# SchemaA.net
KiCad netlist of a schematic drawn in Altium Designer
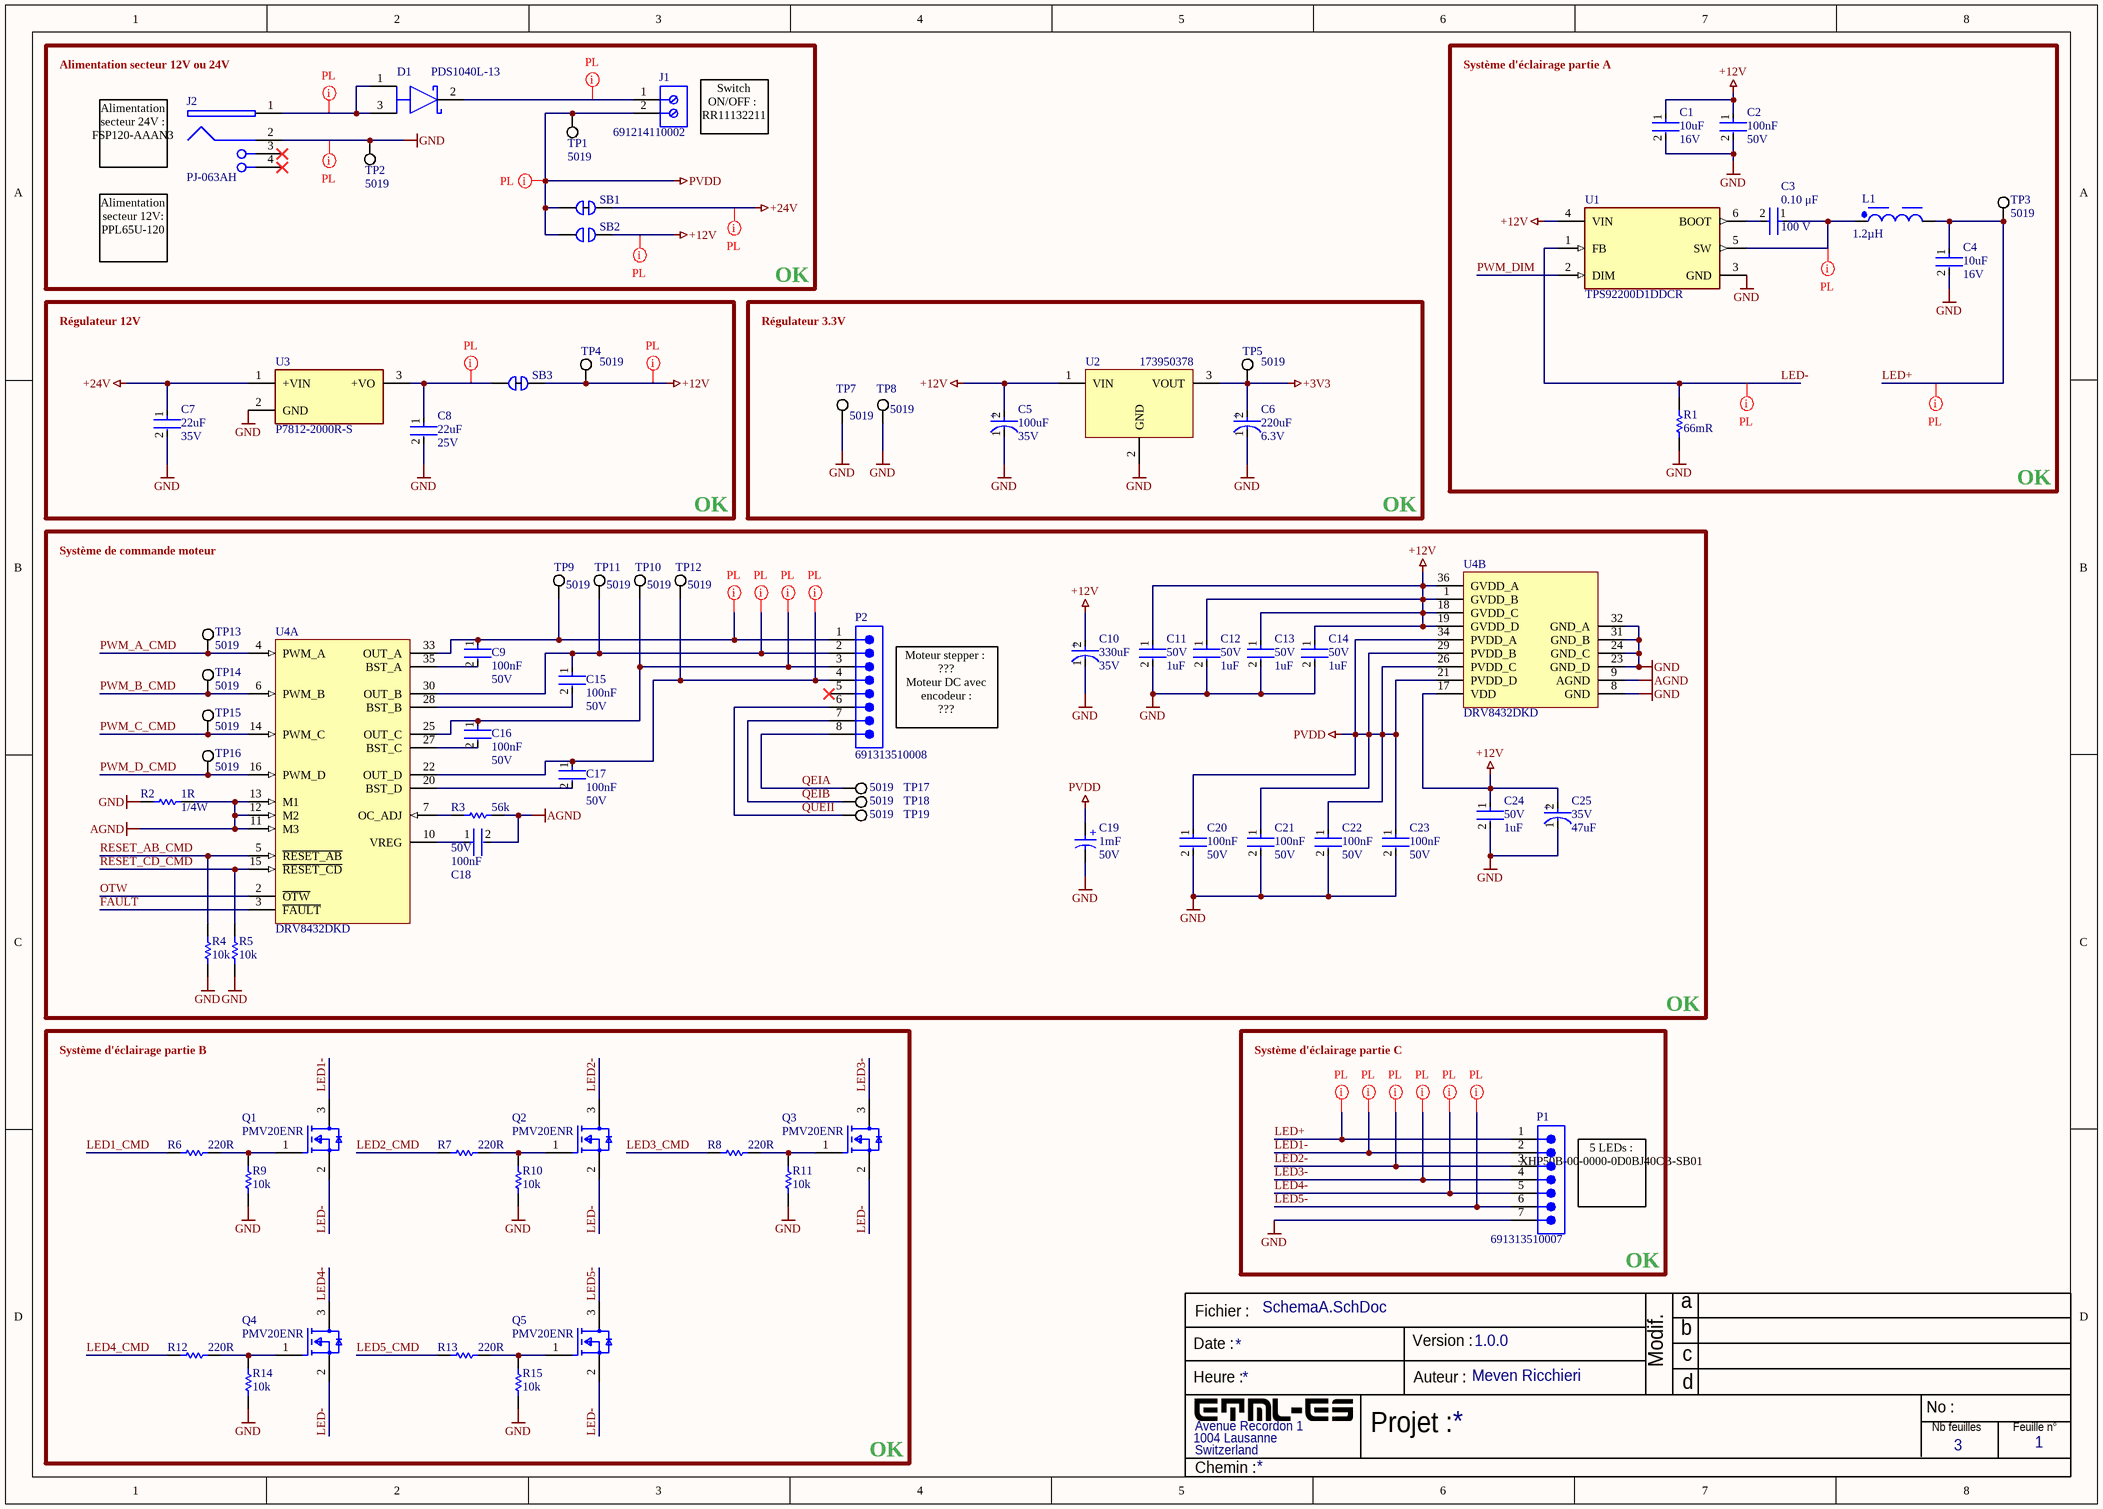
[diagram p0: SchemaA.SchDoc]

(export (version "E")
  (design (tool "Eeschema 10.0.6"))
  (components
    (comp (ref "C1")
      (value "CL21A106KOQNNNE")
      (footprint "FP-CL21-IPC_B")
      (description "CL21 Series 0805 10uF 16V ±10% Tolerance X5R Multilayer Ceramic Chip Capacitor")
      (fields
        (field (name "VOLTAGE") "16V")
        (field (name "CAPACITANCE") "10uF")
        (field (name "VOLTAGE RATING") "16V")
        (field (name "TOLERANCE") "10%")
      )
      (libsource (lib "Altium Content Vault") (part "b4654b650e69147ec39a6b967a45e02"))
    )
    (comp (ref "C2")
      (value "CL21B104KBCNNNC")
      (footprint "FP-CL21-IPC_C")
      (description "CL21 Series 0805 100nF 50V ±10% Tolerance X7R Multilayer Ceramic Chip Capacitor")
      (fields
        (field (name "TOLERANCE") "10%")
        (field (name "CAPACITANCE") "100nF")
        (field (name "VOLTAGE RATING") "50V")
        (field (name "VOLTAGE") "50V")
      )
      (libsource (lib "Altium Content Vault") (part "b4654b650e69147ec39a6b967a45e02"))
    )
    (comp (ref "C3")
      (value "C0805C104K1RACAUTO")
      (footprint "FP-C0805C-DN-MFG")
      (description "CAP CER 0.1UF 100V X7R 0805")
      (fields
        (field (name "MANUFACTURER") "KEMET")
        (field (name "CAPACITANCE") "0.10 μF")
        (field (name "TOLERANCE") "0.1")
        (field (name "VOLTAGE RATING") "100 V")
      )
      (libsource (lib "Altium Content Vault") (part "b4654b650e69147ec39a6b967a45e02"))
    )
    (comp (ref "C4")
      (value "CL21A106KOQNNNE")
      (footprint "FP-CL21-IPC_B")
      (description "CL21 Series 0805 10uF 16V ±10% Tolerance X5R Multilayer Ceramic Chip Capacitor")
      (fields
        (field (name "VOLTAGE") "16V")
        (field (name "CAPACITANCE") "10uF")
        (field (name "VOLTAGE RATING") "16V")
        (field (name "TOLERANCE") "10%")
      )
      (libsource (lib "Altium Content Vault") (part "b4654b650e69147ec39a6b967a45e02"))
    )
    (comp (ref "C5")
      (value "EEE-1VA101XP")
      (footprint "FP-SD8-MFG")
      (description "CAP ALUM 100UF 20% 35V SMD")
      (fields
        (field (name "CAPACITANCE") "100uF")
        (field (name "TOLERANCE") "20%")
        (field (name "VOLTAGE") "35V")
      )
      (libsource (lib "Altium Content Vault") (part "a00bbbee19879c290e62620ae7e47b1"))
    )
    (comp (ref "C6")
      (value "EEE-FK0J221P")
      (footprint "FP-FKD-MFG")
      (description "CAP ALUM 220UF 20% 6.3V SMD")
      (fields
        (field (name "VOLTAGE RATING") "6.3V")
        (field (name "VOLTAGE") "6.3V")
        (field (name "CAPACITANCE") "220uF")
        (field (name "TOLERANCE") "20%")
      )
      (libsource (lib "Altium Content Vault") (part "a00bbbee19879c290e62620ae7e47b1"))
    )
    (comp (ref "C7")
      (value "GMK325BJ226MM-P")
      (footprint "FP-1210-L_3_2_0_3-W_2_5_0-MFG")
      (description "None")
      (fields
        (field (name "CAPACITANCE") "22uF")
        (field (name "VOLTAGE RATING") "35V")
        (field (name "TOLERANCE") "20%")
      )
      (libsource (lib "Altium Content Vault") (part "02cd4be3c70576c341d710602a673aa"))
    )
    (comp (ref "C8")
      (value "22uF")
      (footprint "FP-CL21-IPC_C")
      (description "CL21 Series 0805 22uF 25V ±20% Tolerance X5R Multilayer Ceramic Chip Capacitor")
      (fields (field (name "VOLTAGE") "25V") (field (name "Comment") "CL21A226MAYNNNE"))
      (libsource (lib "Altium Content Vault") (part "b4654b650e69147ec39a6b967a45e02"))
    )
    (comp (ref "C9")
      (value "CL21B104KBCNNNC")
      (footprint "FP-CL21-IPC_C")
      (description "CL21 Series 0805 100nF 50V ±10% Tolerance X7R Multilayer Ceramic Chip Capacitor")
      (fields
        (field (name "TOLERANCE") "10%")
        (field (name "CAPACITANCE") "100nF")
        (field (name "VOLTAGE RATING") "50V")
        (field (name "VOLTAGE") "50V")
      )
      (libsource (lib "Altium Content Vault") (part "b4654b650e69147ec39a6b967a45e02"))
    )
    (comp (ref "C10")
      (value "EEE-1VA331P")
      (footprint "FP-SG-MFG")
      (description "CAP ALUM 330UF 20% 35V SMD")
      (fields
        (field (name "VOLTAGE") "35V")
        (field (name "TOLERANCE") "20%")
        (field (name "CAPACITANCE") "330uF")
      )
      (libsource (lib "Altium Content Vault") (part "a00bbbee19879c290e62620ae7e47b1"))
    )
    (comp (ref "C11")
      (value "CL21B105KBFNNNG")
      (footprint "FP-CL21-IPC_C")
      (description "CL21 Series 0805 1uF 50V ±10% Tolerance X7R Multilayer Ceramic Chip Capacitor")
      (fields
        (field (name "CAPACITANCE") "1uF")
        (field (name "VOLTAGE") "50V")
        (field (name "TOLERANCE") "10%")
      )
      (libsource (lib "Altium Content Vault") (part "b4654b650e69147ec39a6b967a45e02"))
    )
    (comp (ref "C12")
      (value "CL21B105KBFNNNG")
      (footprint "FP-CL21-IPC_C")
      (description "CL21 Series 0805 1uF 50V ±10% Tolerance X7R Multilayer Ceramic Chip Capacitor")
      (fields
        (field (name "CAPACITANCE") "1uF")
        (field (name "VOLTAGE") "50V")
        (field (name "TOLERANCE") "10%")
      )
      (libsource (lib "Altium Content Vault") (part "b4654b650e69147ec39a6b967a45e02"))
    )
    (comp (ref "C13")
      (value "CL21B105KBFNNNG")
      (footprint "FP-CL21-IPC_C")
      (description "CL21 Series 0805 1uF 50V ±10% Tolerance X7R Multilayer Ceramic Chip Capacitor")
      (fields
        (field (name "CAPACITANCE") "1uF")
        (field (name "VOLTAGE") "50V")
        (field (name "TOLERANCE") "10%")
      )
      (libsource (lib "Altium Content Vault") (part "b4654b650e69147ec39a6b967a45e02"))
    )
    (comp (ref "C14")
      (value "CL21B105KBFNNNG")
      (footprint "FP-CL21-IPC_C")
      (description "CL21 Series 0805 1uF 50V ±10% Tolerance X7R Multilayer Ceramic Chip Capacitor")
      (fields
        (field (name "CAPACITANCE") "1uF")
        (field (name "VOLTAGE") "50V")
        (field (name "TOLERANCE") "10%")
      )
      (libsource (lib "Altium Content Vault") (part "b4654b650e69147ec39a6b967a45e02"))
    )
    (comp (ref "C15")
      (value "CL21B104KBCNNNC")
      (footprint "FP-CL21-IPC_C")
      (description "CL21 Series 0805 100nF 50V ±10% Tolerance X7R Multilayer Ceramic Chip Capacitor")
      (fields
        (field (name "TOLERANCE") "10%")
        (field (name "CAPACITANCE") "100nF")
        (field (name "VOLTAGE RATING") "50V")
        (field (name "VOLTAGE") "50V")
      )
      (libsource (lib "Altium Content Vault") (part "b4654b650e69147ec39a6b967a45e02"))
    )
    (comp (ref "C16")
      (value "CL21B104KBCNNNC")
      (footprint "FP-CL21-IPC_C")
      (description "CL21 Series 0805 100nF 50V ±10% Tolerance X7R Multilayer Ceramic Chip Capacitor")
      (fields
        (field (name "TOLERANCE") "10%")
        (field (name "CAPACITANCE") "100nF")
        (field (name "VOLTAGE RATING") "50V")
        (field (name "VOLTAGE") "50V")
      )
      (libsource (lib "Altium Content Vault") (part "b4654b650e69147ec39a6b967a45e02"))
    )
    (comp (ref "C17")
      (value "CL21B104KBCNNNC")
      (footprint "FP-CL21-IPC_C")
      (description "CL21 Series 0805 100nF 50V ±10% Tolerance X7R Multilayer Ceramic Chip Capacitor")
      (fields
        (field (name "TOLERANCE") "10%")
        (field (name "CAPACITANCE") "100nF")
        (field (name "VOLTAGE RATING") "50V")
        (field (name "VOLTAGE") "50V")
      )
      (libsource (lib "Altium Content Vault") (part "b4654b650e69147ec39a6b967a45e02"))
    )
    (comp (ref "C18")
      (value "CL21B104KBCNNNC")
      (footprint "FP-CL21-IPC_C")
      (description "CL21 Series 0805 100nF 50V ±10% Tolerance X7R Multilayer Ceramic Chip Capacitor")
      (fields
        (field (name "TOLERANCE") "10%")
        (field (name "CAPACITANCE") "100nF")
        (field (name "VOLTAGE RATING") "50V")
        (field (name "VOLTAGE") "50V")
      )
      (libsource (lib "Altium Content Vault") (part "b4654b650e69147ec39a6b967a45e02"))
    )
    (comp (ref "C19")
      (value "865080663020")
      (footprint "WCAP-ASLI_D16H17")
      (description "865080663020 WCAP-ASLI Aluminum Electrolytic Capacitors")
      (fields
        (field (name "CAPACITANCE") "1mF")
        (field (name "VOLTAGE RATING") "50V")
        (field (name "TOLERANCE") "20%")
      )
      (libsource (lib "Altium Content Vault") (part "Capacitor_Polarized"))
    )
    (comp (ref "C20")
      (value "CL21B104KBCNNNC")
      (footprint "FP-CL21-IPC_C")
      (description "CL21 Series 0805 100nF 50V ±10% Tolerance X7R Multilayer Ceramic Chip Capacitor")
      (fields
        (field (name "TOLERANCE") "10%")
        (field (name "CAPACITANCE") "100nF")
        (field (name "VOLTAGE RATING") "50V")
        (field (name "VOLTAGE") "50V")
      )
      (libsource (lib "Altium Content Vault") (part "b4654b650e69147ec39a6b967a45e02"))
    )
    (comp (ref "C21")
      (value "CL21B104KBCNNNC")
      (footprint "FP-CL21-IPC_C")
      (description "CL21 Series 0805 100nF 50V ±10% Tolerance X7R Multilayer Ceramic Chip Capacitor")
      (fields
        (field (name "TOLERANCE") "10%")
        (field (name "CAPACITANCE") "100nF")
        (field (name "VOLTAGE RATING") "50V")
        (field (name "VOLTAGE") "50V")
      )
      (libsource (lib "Altium Content Vault") (part "b4654b650e69147ec39a6b967a45e02"))
    )
    (comp (ref "C22")
      (value "CL21B104KBCNNNC")
      (footprint "FP-CL21-IPC_C")
      (description "CL21 Series 0805 100nF 50V ±10% Tolerance X7R Multilayer Ceramic Chip Capacitor")
      (fields
        (field (name "TOLERANCE") "10%")
        (field (name "CAPACITANCE") "100nF")
        (field (name "VOLTAGE RATING") "50V")
        (field (name "VOLTAGE") "50V")
      )
      (libsource (lib "Altium Content Vault") (part "b4654b650e69147ec39a6b967a45e02"))
    )
    (comp (ref "C23")
      (value "CL21B104KBCNNNC")
      (footprint "FP-CL21-IPC_C")
      (description "CL21 Series 0805 100nF 50V ±10% Tolerance X7R Multilayer Ceramic Chip Capacitor")
      (fields
        (field (name "TOLERANCE") "10%")
        (field (name "CAPACITANCE") "100nF")
        (field (name "VOLTAGE RATING") "50V")
        (field (name "VOLTAGE") "50V")
      )
      (libsource (lib "Altium Content Vault") (part "b4654b650e69147ec39a6b967a45e02"))
    )
    (comp (ref "C24")
      (value "CL21B105KBFNNNG")
      (footprint "FP-CL21-IPC_C")
      (description "CL21 Series 0805 1uF 50V ±10% Tolerance X7R Multilayer Ceramic Chip Capacitor")
      (fields
        (field (name "CAPACITANCE") "1uF")
        (field (name "VOLTAGE") "50V")
        (field (name "TOLERANCE") "10%")
      )
      (libsource (lib "Altium Content Vault") (part "b4654b650e69147ec39a6b967a45e02"))
    )
    (comp (ref "C25")
      (value "EEEFP1V470AP")
      (footprint "FP-FPD-MFG")
      (description "CAP ALUM 47UF 20% 35V SMD")
      (fields
        (field (name "VOLTAGE RATING (DC)") "35V")
        (field (name "TOLERANCE") "20%")
        (field (name "CAPACITANCE") "47uF")
        (field (name "VOLTAGE") "35V")
      )
      (libsource (lib "Altium Content Vault") (part "cf48714ba7e38822c1575c7ec0b6d1f"))
    )
    (comp (ref "D1")
      (value "PDS1040L-13")
      (footprint "FP-PowerDI5-MFG")
      (description "DIODE SCHOTTKY 40V 10A POWERDI5")
      (fields
        (field (name "OCTOPART") "https://octopart.com/pds1040l-13-diodes+inc.-332540")
        (field (name "MANUFACTURER") "Diodes Inc.")
      )
      (libsource (lib "Altium Content Vault") (part "742f7ab95c42997246ebbe41a6c66ae"))
    )
    (comp (ref "J1")
      (value "691214110002")
      (footprint "691214110002")
      (fields (field (name "VOLTAGE") "300V"))
      (libsource (lib "Altium Content Vault") (part "TBL - 1R - 02P - Screw"))
    )
    (comp (ref "J2")
      (value "PJ-063AH")
      (footprint "CUI-PJ-063AH_V")
      (fields (field (name "MANUFACTURER") "CUIInc."))
      (libsource (lib "Altium Content Vault") (part "JACK-2CD2_A"))
    )
    (comp (ref "L1")
      (value "7440430012")
      (footprint "WE-TPC_4828")
      (fields (field (name "TOLERANCE") "30%") (field (name "INDUCTANCE") "1.2µH"))
      (libsource (lib "Altium Content Vault") (part "Inductor - 2"))
    )
    (comp (ref "P1")
      (value "691313510007")
      (footprint "691313510007")
      (libsource (lib "Altium Content Vault") (part "TBL - 1R - 07P - Male"))
    )
    (comp (ref "P2")
      (value "691313510008")
      (footprint "691313510008")
      (fields (field (name "VOLTAGE") "300V"))
      (libsource (lib "Altium Content Vault") (part "TBL - 1R - 08P - Male"))
    )
    (comp (ref "Q1")
      (value "PMV20ENR")
      (footprint "FP-SOT23-MFG")
      (description "MOSFET N-CH 30V SOT23")
      (libsource (lib "Altium Content Vault") (part "0a9ea7c96deaaede766a5b531c28de0"))
    )
    (comp (ref "Q2")
      (value "PMV20ENR")
      (footprint "FP-SOT23-MFG")
      (description "MOSFET N-CH 30V SOT23")
      (libsource (lib "Altium Content Vault") (part "0a9ea7c96deaaede766a5b531c28de0"))
    )
    (comp (ref "Q3")
      (value "PMV20ENR")
      (footprint "FP-SOT23-MFG")
      (description "MOSFET N-CH 30V SOT23")
      (libsource (lib "Altium Content Vault") (part "0a9ea7c96deaaede766a5b531c28de0"))
    )
    (comp (ref "Q4")
      (value "PMV20ENR")
      (footprint "FP-SOT23-MFG")
      (description "MOSFET N-CH 30V SOT23")
      (libsource (lib "Altium Content Vault") (part "0a9ea7c96deaaede766a5b531c28de0"))
    )
    (comp (ref "Q5")
      (value "PMV20ENR")
      (footprint "FP-SOT23-MFG")
      (description "MOSFET N-CH 30V SOT23")
      (libsource (lib "Altium Content Vault") (part "0a9ea7c96deaaede766a5b531c28de0"))
    )
    (comp (ref "R1")
      (value "66mR")
      (footprint "6-0805_M")
      (description "Resistor")
      (fields (field (name "Comment") "ERJ-L06UF66MV") (field (name "PUBLISHER") "Altium Limited"))
      (libsource (lib "Miscellaneous Devices") (part "Res1"))
    )
    (comp (ref "R2")
      (value "1R")
      (footprint "RESC2013X60X30NL20T20")
      (fields
        (field (name "MANUFACTURER") "KOA Speer")
        (field (name "PART NUMBER") "RK73B2ATTD1R0J")
        (field (name "POWER") "1/4W")
      )
      (libsource (lib "Altium Content Vault") (part "RES"))
    )
    (comp (ref "R3")
      (value "56k")
      (footprint "RESC2013X70X40NL20T20")
      (fields (field (name "PART NUMBER") "ERJ6ENF5602V") (field (name "MANUFACTURER") "Panasonic"))
      (libsource (lib "Altium Content Vault") (part "RES"))
    )
    (comp (ref "R4")
      (value "RC0805JR-0710KL")
      (footprint "RESC2013X60X35ML10T20")
      (description "Chip Resistor, 10 KOhm, +/- 5%, 0.125 W, -55 to 155 degC, 0805 (2012 Metric), RoHS, Tape and Reel")
      (fields (field (name "MANUFACTURER") "Yageo") (field (name "RESISTANCE") "10k"))
      (libsource (lib "Altium Content Vault") (part "RES-2"))
    )
    (comp (ref "R5")
      (value "RC0805JR-0710KL")
      (footprint "RESC2013X60X35ML10T20")
      (description "Chip Resistor, 10 KOhm, +/- 5%, 0.125 W, -55 to 155 degC, 0805 (2012 Metric), RoHS, Tape and Reel")
      (fields (field (name "MANUFACTURER") "Yageo") (field (name "RESISTANCE") "10k"))
      (libsource (lib "Altium Content Vault") (part "RES-2"))
    )
    (comp (ref "R6")
      (value "220R")
      (footprint "RESC2013X70X40NL20T20")
      (fields (field (name "PART NUMBER") "ERJ6ENF2200V") (field (name "MANUFACTURER") "Panasonic"))
      (libsource (lib "Altium Content Vault") (part "RES"))
    )
    (comp (ref "R7")
      (value "220R")
      (footprint "RESC2013X70X40NL20T20")
      (fields (field (name "PART NUMBER") "ERJ6ENF2200V") (field (name "MANUFACTURER") "Panasonic"))
      (libsource (lib "Altium Content Vault") (part "RES"))
    )
    (comp (ref "R8")
      (value "220R")
      (footprint "RESC2013X70X40NL20T20")
      (fields (field (name "PART NUMBER") "ERJ6ENF2200V") (field (name "MANUFACTURER") "Panasonic"))
      (libsource (lib "Altium Content Vault") (part "RES"))
    )
    (comp (ref "R9")
      (value "RC0805JR-0710KL")
      (footprint "RESC2013X60X35ML10T20")
      (description "Chip Resistor, 10 KOhm, +/- 5%, 0.125 W, -55 to 155 degC, 0805 (2012 Metric), RoHS, Tape and Reel")
      (fields (field (name "MANUFACTURER") "Yageo") (field (name "RESISTANCE") "10k"))
      (libsource (lib "Altium Content Vault") (part "RES-2"))
    )
    (comp (ref "R10")
      (value "RC0805JR-0710KL")
      (footprint "RESC2013X60X35ML10T20")
      (description "Chip Resistor, 10 KOhm, +/- 5%, 0.125 W, -55 to 155 degC, 0805 (2012 Metric), RoHS, Tape and Reel")
      (fields (field (name "MANUFACTURER") "Yageo") (field (name "RESISTANCE") "10k"))
      (libsource (lib "Altium Content Vault") (part "RES-2"))
    )
    (comp (ref "R11")
      (value "RC0805JR-0710KL")
      (footprint "RESC2013X60X35ML10T20")
      (description "Chip Resistor, 10 KOhm, +/- 5%, 0.125 W, -55 to 155 degC, 0805 (2012 Metric), RoHS, Tape and Reel")
      (fields (field (name "MANUFACTURER") "Yageo") (field (name "RESISTANCE") "10k"))
      (libsource (lib "Altium Content Vault") (part "RES-2"))
    )
    (comp (ref "R12")
      (value "220R")
      (footprint "RESC2013X70X40NL20T20")
      (fields (field (name "PART NUMBER") "ERJ6ENF2200V") (field (name "MANUFACTURER") "Panasonic"))
      (libsource (lib "Altium Content Vault") (part "RES"))
    )
    (comp (ref "R13")
      (value "220R")
      (footprint "RESC2013X70X40NL20T20")
      (fields (field (name "PART NUMBER") "ERJ6ENF2200V") (field (name "MANUFACTURER") "Panasonic"))
      (libsource (lib "Altium Content Vault") (part "RES"))
    )
    (comp (ref "R14")
      (value "RC0805JR-0710KL")
      (footprint "RESC2013X60X35ML10T20")
      (description "Chip Resistor, 10 KOhm, +/- 5%, 0.125 W, -55 to 155 degC, 0805 (2012 Metric), RoHS, Tape and Reel")
      (fields (field (name "MANUFACTURER") "Yageo") (field (name "RESISTANCE") "10k"))
      (libsource (lib "Altium Content Vault") (part "RES-2"))
    )
    (comp (ref "R15")
      (value "RC0805JR-0710KL")
      (footprint "RESC2013X60X35ML10T20")
      (description "Chip Resistor, 10 KOhm, +/- 5%, 0.125 W, -55 to 155 degC, 0805 (2012 Metric), RoHS, Tape and Reel")
      (fields (field (name "MANUFACTURER") "Yageo") (field (name "RESISTANCE") "10k"))
      (libsource (lib "Altium Content Vault") (part "RES-2"))
    )
    (comp (ref "SB1")
      (value "Solder bridge 3mm close")
      (footprint "Solder bridge")
      (libsource (lib "SymbLib") (part "Solder bridge 3mm close"))
    )
    (comp (ref "SB2")
      (value "Solder bridge 3mm open")
      (footprint "Solder bridge")
      (libsource (lib "SymbLib") (part "Solder bridge 3mm open"))
    )
    (comp (ref "SB3")
      (value "Solder bridge 3mm close")
      (footprint "Solder bridge")
      (libsource (lib "SymbLib") (part "Solder bridge 3mm close"))
    )
    (comp (ref "TP1")
      (value "5019")
      (footprint "KSTN-5019_V")
      (description "Test Point, 1 Position SMD, RoHS, Tape and Reel")
      (libsource (lib "Altium Content Vault") (part "TESTPOINT_WHITE"))
    )
    (comp (ref "TP2")
      (value "5019")
      (footprint "KSTN-5019_V")
      (description "Test Point, 1 Position SMD, RoHS, Tape and Reel")
      (libsource (lib "Altium Content Vault") (part "TESTPOINT_WHITE"))
    )
    (comp (ref "TP3")
      (value "5019")
      (footprint "KSTN-5019_V")
      (description "Test Point, 1 Position SMD, RoHS, Tape and Reel")
      (libsource (lib "Altium Content Vault") (part "TESTPOINT_WHITE"))
    )
    (comp (ref "TP4")
      (value "5019")
      (footprint "KSTN-5019_V")
      (description "Test Point, 1 Position SMD, RoHS, Tape and Reel")
      (libsource (lib "Altium Content Vault") (part "TESTPOINT_WHITE"))
    )
    (comp (ref "TP5")
      (value "5019")
      (footprint "KSTN-5019_V")
      (description "Test Point, 1 Position SMD, RoHS, Tape and Reel")
      (libsource (lib "Altium Content Vault") (part "TESTPOINT_WHITE"))
    )
    (comp (ref "TP7")
      (value "5019")
      (footprint "KSTN-5019_V")
      (description "Test Point, 1 Position SMD, RoHS, Tape and Reel")
      (libsource (lib "Altium Content Vault") (part "TESTPOINT_WHITE"))
    )
    (comp (ref "TP8")
      (value "5019")
      (footprint "KSTN-5019_V")
      (description "Test Point, 1 Position SMD, RoHS, Tape and Reel")
      (libsource (lib "Altium Content Vault") (part "TESTPOINT_WHITE"))
    )
    (comp (ref "TP9")
      (value "5019")
      (footprint "KSTN-5019_V")
      (description "Test Point, 1 Position SMD, RoHS, Tape and Reel")
      (libsource (lib "Altium Content Vault") (part "TESTPOINT_WHITE"))
    )
    (comp (ref "TP10")
      (value "5019")
      (footprint "KSTN-5019_V")
      (description "Test Point, 1 Position SMD, RoHS, Tape and Reel")
      (libsource (lib "Altium Content Vault") (part "TESTPOINT_WHITE"))
    )
    (comp (ref "TP11")
      (value "5019")
      (footprint "KSTN-5019_V")
      (description "Test Point, 1 Position SMD, RoHS, Tape and Reel")
      (libsource (lib "Altium Content Vault") (part "TESTPOINT_WHITE"))
    )
    (comp (ref "TP12")
      (value "5019")
      (footprint "KSTN-5019_V")
      (description "Test Point, 1 Position SMD, RoHS, Tape and Reel")
      (libsource (lib "Altium Content Vault") (part "TESTPOINT_WHITE"))
    )
    (comp (ref "TP13")
      (value "5019")
      (footprint "KSTN-5019_V")
      (description "Test Point, 1 Position SMD, RoHS, Tape and Reel")
      (libsource (lib "Altium Content Vault") (part "TESTPOINT_WHITE"))
    )
    (comp (ref "TP14")
      (value "5019")
      (footprint "KSTN-5019_V")
      (description "Test Point, 1 Position SMD, RoHS, Tape and Reel")
      (libsource (lib "Altium Content Vault") (part "TESTPOINT_WHITE"))
    )
    (comp (ref "TP15")
      (value "5019")
      (footprint "KSTN-5019_V")
      (description "Test Point, 1 Position SMD, RoHS, Tape and Reel")
      (libsource (lib "Altium Content Vault") (part "TESTPOINT_WHITE"))
    )
    (comp (ref "TP16")
      (value "5019")
      (footprint "KSTN-5019_V")
      (description "Test Point, 1 Position SMD, RoHS, Tape and Reel")
      (libsource (lib "Altium Content Vault") (part "TESTPOINT_WHITE"))
    )
    (comp (ref "TP17")
      (value "5019")
      (footprint "KSTN-5019_V")
      (description "Test Point, 1 Position SMD, RoHS, Tape and Reel")
      (libsource (lib "Altium Content Vault") (part "TESTPOINT_WHITE"))
    )
    (comp (ref "TP18")
      (value "5019")
      (footprint "KSTN-5019_V")
      (description "Test Point, 1 Position SMD, RoHS, Tape and Reel")
      (libsource (lib "Altium Content Vault") (part "TESTPOINT_WHITE"))
    )
    (comp (ref "TP19")
      (value "5019")
      (footprint "KSTN-5019_V")
      (description "Test Point, 1 Position SMD, RoHS, Tape and Reel")
      (libsource (lib "Altium Content Vault") (part "TESTPOINT_WHITE"))
    )
    (comp (ref "U1")
      (value "TPS92200D1DDCR")
      (footprint "FP-DDC0006A-MFG")
      (libsource (lib "Altium Content Vault") (part "587de3e5279691f4f220b4264879a86"))
    )
    (comp (ref "U2")
      (value "173950378")
      (footprint "WPME-FDSM_SIP-3_L11.6W8.5H10.5")
      (description "173950378 Module DC-DC 1-OUT 3.3V 0.5A 3-Pin SIP Module Tube")
      (libsource (lib "Altium Content Vault") (part "SIP-3_WPME-FDSM"))
    )
    (comp (ref "U3")
      (value "P7812-2000R-S")
      (footprint "P7812-2000R-S")
      (libsource (lib "SymbLib") (part "P7812-2000R-S"))
    )
    (comp (ref "U4")
      (value "DRV8432DKD")
      (footprint "SOP65P1420X360-36N")
      (libsource (lib "SymbLib") (part "DRV8432DKD"))
    )
  )
  (nets
    (net (code "1") (name "+3V3") (class "Default")
      (node (ref "C6") (pin "2") (pinfunction "A_2") (pintype "passive"))
      (node (ref "TP5") (pin "1") (pinfunction "1_1") (pintype "passive"))
      (node (ref "U2") (pin "3") (pinfunction "VOUT_3") (pintype "passive"))
    )
    (net (code "2") (name "+12V") (class "Default")
      (node (ref "C1") (pin "1") (pinfunction "1_1") (pintype "passive"))
      (node (ref "C10") (pin "2") (pinfunction "A_2") (pintype "passive"))
      (node (ref "C11") (pin "1") (pinfunction "1_1") (pintype "passive"))
      (node (ref "C12") (pin "1") (pinfunction "1_1") (pintype "passive"))
      (node (ref "C13") (pin "1") (pinfunction "1_1") (pintype "passive"))
      (node (ref "C14") (pin "1") (pinfunction "1_1") (pintype "passive"))
      (node (ref "C2") (pin "1") (pinfunction "1_1") (pintype "passive"))
      (node (ref "C24") (pin "1") (pinfunction "1_1") (pintype "passive"))
      (node (ref "C25") (pin "2") (pinfunction "A_2") (pintype "passive"))
      (node (ref "C5") (pin "2") (pinfunction "A_2") (pintype "passive"))
      (node (ref "SB2") (pin "2") (pinfunction "2_2") (pintype "passive"))
      (node (ref "SB3") (pin "2") (pinfunction "2_2") (pintype "passive"))
      (node (ref "TP4") (pin "1") (pinfunction "1_1") (pintype "passive"))
      (node (ref "U1") (pin "4") (pinfunction "VIN_4") (pintype "power_in"))
      (node (ref "U2") (pin "1") (pinfunction "VIN_1") (pintype "passive"))
      (node (ref "U4") (pin "1") (pinfunction "GVDD_B_1") (pintype "power_in"))
      (node (ref "U4") (pin "17") (pinfunction "VDD_17") (pintype "power_in"))
      (node (ref "U4") (pin "18") (pinfunction "GVDD_C_18") (pintype "power_in"))
      (node (ref "U4") (pin "19") (pinfunction "GVDD_D_19") (pintype "power_in"))
      (node (ref "U4") (pin "36") (pinfunction "GVDD_A_36") (pintype "power_in"))
    )
    (net (code "3") (name "+24V") (class "Default")
      (node (ref "C7") (pin "1") (pinfunction "1_1") (pintype "passive"))
      (node (ref "SB1") (pin "2") (pinfunction "2_2") (pintype "passive"))
      (node (ref "U3") (pin "1") (pinfunction "+VIN_1") (pintype "passive"))
    )
    (net (code "4") (name "/FAULT") (class "Default")
      (node (ref "U4") (pin "3") (pinfunction "~{FAULT}_3") (pintype "open_collector"))
    )
    (net (code "5") (name "/LED+") (class "Default")
      (node (ref "C4") (pin "1") (pinfunction "1_1") (pintype "passive"))
      (node (ref "L1") (pin "2") (pinfunction "2_2") (pintype "passive"))
      (node (ref "P1") (pin "1") (pinfunction "1_1") (pintype "passive"))
      (node (ref "TP3") (pin "1") (pinfunction "1_1") (pintype "passive"))
    )
    (net (code "6") (name "/LED-") (class "Default")
      (node (ref "Q1") (pin "2") (pinfunction "S_2") (pintype "passive"))
      (node (ref "Q2") (pin "2") (pinfunction "S_2") (pintype "passive"))
      (node (ref "Q3") (pin "2") (pinfunction "S_2") (pintype "passive"))
      (node (ref "Q4") (pin "2") (pinfunction "S_2") (pintype "passive"))
      (node (ref "Q5") (pin "2") (pinfunction "S_2") (pintype "passive"))
      (node (ref "R1") (pin "2") (pinfunction "2_2") (pintype "passive"))
      (node (ref "U1") (pin "1") (pinfunction "FB_1") (pintype "input"))
    )
    (net (code "7") (name "/LED1-") (class "Default")
      (node (ref "P1") (pin "2") (pinfunction "2_2") (pintype "passive"))
      (node (ref "Q1") (pin "3") (pinfunction "D_3") (pintype "passive"))
    )
    (net (code "8") (name "/LED1_CMD") (class "Default")
      (node (ref "R6") (pin "1") (pinfunction "1_1") (pintype "passive"))
    )
    (net (code "9") (name "/LED2-") (class "Default")
      (node (ref "P1") (pin "3") (pinfunction "3_3") (pintype "passive"))
      (node (ref "Q2") (pin "3") (pinfunction "D_3") (pintype "passive"))
    )
    (net (code "10") (name "/LED2_CMD") (class "Default")
      (node (ref "R7") (pin "1") (pinfunction "1_1") (pintype "passive"))
    )
    (net (code "11") (name "/LED3-") (class "Default")
      (node (ref "P1") (pin "4") (pinfunction "4_4") (pintype "passive"))
      (node (ref "Q3") (pin "3") (pinfunction "D_3") (pintype "passive"))
    )
    (net (code "12") (name "/LED3_CMD") (class "Default")
      (node (ref "R8") (pin "1") (pinfunction "1_1") (pintype "passive"))
    )
    (net (code "13") (name "/LED4-") (class "Default")
      (node (ref "P1") (pin "5") (pinfunction "5_5") (pintype "passive"))
      (node (ref "Q4") (pin "3") (pinfunction "D_3") (pintype "passive"))
    )
    (net (code "14") (name "/LED4_CMD") (class "Default")
      (node (ref "R12") (pin "1") (pinfunction "1_1") (pintype "passive"))
    )
    (net (code "15") (name "/LED5-") (class "Default")
      (node (ref "P1") (pin "6") (pinfunction "6_6") (pintype "passive"))
      (node (ref "Q5") (pin "3") (pinfunction "D_3") (pintype "passive"))
    )
    (net (code "16") (name "/LED5_CMD") (class "Default")
      (node (ref "R13") (pin "1") (pinfunction "1_1") (pintype "passive"))
    )
    (net (code "17") (name "/OTW") (class "Default")
      (node (ref "U4") (pin "2") (pinfunction "~{OTW}_2") (pintype "open_collector"))
    )
    (net (code "18") (name "/PWM_A_CMD") (class "Default")
      (node (ref "TP13") (pin "1") (pinfunction "1_1") (pintype "passive"))
      (node (ref "U4") (pin "4") (pinfunction "PWM_A_4") (pintype "input"))
    )
    (net (code "19") (name "/PWM_B_CMD") (class "Default")
      (node (ref "TP14") (pin "1") (pinfunction "1_1") (pintype "passive"))
      (node (ref "U4") (pin "6") (pinfunction "PWM_B_6") (pintype "input"))
    )
    (net (code "20") (name "/PWM_C_CMD") (class "Default")
      (node (ref "TP15") (pin "1") (pinfunction "1_1") (pintype "passive"))
      (node (ref "U4") (pin "14") (pinfunction "PWM_C_14") (pintype "input"))
    )
    (net (code "21") (name "/PWM_DIM") (class "Default")
      (node (ref "U1") (pin "2") (pinfunction "DIM_2") (pintype "input"))
    )
    (net (code "22") (name "/PWM_D_CMD") (class "Default")
      (node (ref "TP16") (pin "1") (pinfunction "1_1") (pintype "passive"))
      (node (ref "U4") (pin "16") (pinfunction "PWM_D_16") (pintype "input"))
    )
    (net (code "23") (name "/QEIA") (class "Default")
      (node (ref "P2") (pin "8") (pinfunction "8_8") (pintype "passive"))
      (node (ref "TP17") (pin "1") (pinfunction "1_1") (pintype "passive"))
    )
    (net (code "24") (name "/QEIB") (class "Default")
      (node (ref "P2") (pin "7") (pinfunction "7_7") (pintype "passive"))
      (node (ref "TP18") (pin "1") (pinfunction "1_1") (pintype "passive"))
    )
    (net (code "25") (name "/QUEII") (class "Default")
      (node (ref "P2") (pin "6") (pinfunction "6_6") (pintype "passive"))
      (node (ref "TP19") (pin "1") (pinfunction "1_1") (pintype "passive"))
    )
    (net (code "26") (name "/RESET_AB_CMD") (class "Default")
      (node (ref "R4") (pin "2") (pinfunction "2_2") (pintype "passive"))
      (node (ref "U4") (pin "5") (pinfunction "~{RESET_AB}_5") (pintype "input"))
    )
    (net (code "27") (name "/RESET_CD_CMD") (class "Default")
      (node (ref "R5") (pin "2") (pinfunction "2_2") (pintype "passive"))
      (node (ref "U4") (pin "15") (pinfunction "~{RESET_CD}_15") (pintype "input"))
    )
    (net (code "28") (name "AGND") (class "Default")
      (node (ref "C18") (pin "2") (pinfunction "2_2") (pintype "passive"))
      (node (ref "R2") (pin "2") (pinfunction "2_2") (pintype "passive"))
      (node (ref "R3") (pin "2") (pinfunction "2_2") (pintype "passive"))
      (node (ref "U4") (pin "11") (pinfunction "M3_11") (pintype "input"))
      (node (ref "U4") (pin "12") (pinfunction "M2_12") (pintype "input"))
      (node (ref "U4") (pin "13") (pinfunction "M1_13") (pintype "input"))
      (node (ref "U4") (pin "9") (pinfunction "AGND_9") (pintype "power_in"))
    )
    (net (code "29") (name "GND") (class "Default")
      (node (ref "C1") (pin "2") (pinfunction "2_2") (pintype "passive"))
      (node (ref "C10") (pin "1") (pinfunction "C_1") (pintype "passive"))
      (node (ref "C11") (pin "2") (pinfunction "2_2") (pintype "passive"))
      (node (ref "C12") (pin "2") (pinfunction "2_2") (pintype "passive"))
      (node (ref "C13") (pin "2") (pinfunction "2_2") (pintype "passive"))
      (node (ref "C14") (pin "2") (pinfunction "2_2") (pintype "passive"))
      (node (ref "C19") (pin "2") (pinfunction "N_2") (pintype "passive"))
      (node (ref "C2") (pin "2") (pinfunction "2_2") (pintype "passive"))
      (node (ref "C20") (pin "2") (pinfunction "2_2") (pintype "passive"))
      (node (ref "C21") (pin "2") (pinfunction "2_2") (pintype "passive"))
      (node (ref "C22") (pin "2") (pinfunction "2_2") (pintype "passive"))
      (node (ref "C23") (pin "2") (pinfunction "2_2") (pintype "passive"))
      (node (ref "C24") (pin "2") (pinfunction "2_2") (pintype "passive"))
      (node (ref "C25") (pin "1") (pinfunction "C_1") (pintype "passive"))
      (node (ref "C4") (pin "2") (pinfunction "2_2") (pintype "passive"))
      (node (ref "C5") (pin "1") (pinfunction "C_1") (pintype "passive"))
      (node (ref "C6") (pin "1") (pinfunction "C_1") (pintype "passive"))
      (node (ref "C7") (pin "2") (pinfunction "2_2") (pintype "passive"))
      (node (ref "C8") (pin "2") (pinfunction "2_2") (pintype "passive"))
      (node (ref "J2") (pin "2") (pinfunction "2_2") (pintype "passive"))
      (node (ref "P1") (pin "7") (pinfunction "7_7") (pintype "passive"))
      (node (ref "R1") (pin "1") (pinfunction "1_1") (pintype "passive"))
      (node (ref "R10") (pin "1") (pinfunction "1_1") (pintype "passive"))
      (node (ref "R11") (pin "1") (pinfunction "1_1") (pintype "passive"))
      (node (ref "R14") (pin "1") (pinfunction "1_1") (pintype "passive"))
      (node (ref "R15") (pin "1") (pinfunction "1_1") (pintype "passive"))
      (node (ref "R2") (pin "1") (pinfunction "1_1") (pintype "passive"))
      (node (ref "R4") (pin "1") (pinfunction "1_1") (pintype "passive"))
      (node (ref "R5") (pin "1") (pinfunction "1_1") (pintype "passive"))
      (node (ref "R9") (pin "1") (pinfunction "1_1") (pintype "passive"))
      (node (ref "TP2") (pin "1") (pinfunction "1_1") (pintype "passive"))
      (node (ref "TP7") (pin "1") (pinfunction "1_1") (pintype "passive"))
      (node (ref "TP8") (pin "1") (pinfunction "1_1") (pintype "passive"))
      (node (ref "U1") (pin "3") (pinfunction "GND_3") (pintype "power_in"))
      (node (ref "U2") (pin "2") (pinfunction "GND_2") (pintype "passive"))
      (node (ref "U3") (pin "2") (pinfunction "GND_2") (pintype "power_in"))
      (node (ref "U4") (pin "23") (pinfunction "GND_D_23") (pintype "power_in"))
      (node (ref "U4") (pin "24") (pinfunction "GND_C_24") (pintype "power_in"))
      (node (ref "U4") (pin "31") (pinfunction "GND_B_31") (pintype "power_in"))
      (node (ref "U4") (pin "32") (pinfunction "GND_A_32") (pintype "power_in"))
      (node (ref "U4") (pin "8") (pinfunction "GND_8") (pintype "power_in"))
    )
    (net (code "30") (name "Net-(D1-A-Pad1)") (class "Default")
      (node (ref "D1") (pin "1") (pinfunction "A_1") (pintype "passive"))
      (node (ref "D1") (pin "3") (pinfunction "A_3") (pintype "passive"))
      (node (ref "J2") (pin "1") (pinfunction "1_1") (pintype "passive"))
    )
    (net (code "31") (name "Net-(D1-C)") (class "Default")
      (node (ref "D1") (pin "2") (pinfunction "C_2") (pintype "passive"))
      (node (ref "J1") (pin "1") (pinfunction "1_1") (pintype "passive"))
    )
    (net (code "32") (name "Net-(Q1-G)") (class "Default")
      (node (ref "Q1") (pin "1") (pinfunction "G_1") (pintype "passive"))
      (node (ref "R6") (pin "2") (pinfunction "2_2") (pintype "passive"))
      (node (ref "R9") (pin "2") (pinfunction "2_2") (pintype "passive"))
    )
    (net (code "33") (name "Net-(Q2-G)") (class "Default")
      (node (ref "Q2") (pin "1") (pinfunction "G_1") (pintype "passive"))
      (node (ref "R10") (pin "2") (pinfunction "2_2") (pintype "passive"))
      (node (ref "R7") (pin "2") (pinfunction "2_2") (pintype "passive"))
    )
    (net (code "34") (name "Net-(Q3-G)") (class "Default")
      (node (ref "Q3") (pin "1") (pinfunction "G_1") (pintype "passive"))
      (node (ref "R11") (pin "2") (pinfunction "2_2") (pintype "passive"))
      (node (ref "R8") (pin "2") (pinfunction "2_2") (pintype "passive"))
    )
    (net (code "35") (name "Net-(Q4-G)") (class "Default")
      (node (ref "Q4") (pin "1") (pinfunction "G_1") (pintype "passive"))
      (node (ref "R12") (pin "2") (pinfunction "2_2") (pintype "passive"))
      (node (ref "R14") (pin "2") (pinfunction "2_2") (pintype "passive"))
    )
    (net (code "36") (name "Net-(Q5-G)") (class "Default")
      (node (ref "Q5") (pin "1") (pinfunction "G_1") (pintype "passive"))
      (node (ref "R13") (pin "2") (pinfunction "2_2") (pintype "passive"))
      (node (ref "R15") (pin "2") (pinfunction "2_2") (pintype "passive"))
    )
    (net (code "37") (name "Net-(U1-BOOT)") (class "Default")
      (node (ref "C3") (pin "2") (pinfunction "2_2") (pintype "passive"))
      (node (ref "U1") (pin "6") (pinfunction "BOOT_6") (pintype "output"))
    )
    (net (code "38") (name "Net-(U1-SW)") (class "Default")
      (node (ref "C3") (pin "1") (pinfunction "1_1") (pintype "passive"))
      (node (ref "L1") (pin "1") (pinfunction "1_1") (pintype "passive"))
      (node (ref "U1") (pin "5") (pinfunction "SW_5") (pintype "output"))
    )
    (net (code "39") (name "Net-(U3-+VO)") (class "Default")
      (node (ref "C8") (pin "1") (pinfunction "1_1") (pintype "passive"))
      (node (ref "SB3") (pin "1") (pinfunction "1_1") (pintype "passive"))
      (node (ref "U3") (pin "3") (pinfunction "+VO_3") (pintype "passive"))
    )
    (net (code "40") (name "Net-(U4A-BST_A)") (class "Default")
      (node (ref "C9") (pin "2") (pinfunction "2_2") (pintype "passive"))
      (node (ref "U4") (pin "35") (pinfunction "BST_A_35") (pintype "passive"))
    )
    (net (code "41") (name "Net-(U4A-BST_B)") (class "Default")
      (node (ref "C15") (pin "2") (pinfunction "2_2") (pintype "passive"))
      (node (ref "U4") (pin "28") (pinfunction "BST_B_28") (pintype "passive"))
    )
    (net (code "42") (name "Net-(U4A-BST_C)") (class "Default")
      (node (ref "C16") (pin "2") (pinfunction "2_2") (pintype "passive"))
      (node (ref "U4") (pin "27") (pinfunction "BST_C_27") (pintype "passive"))
    )
    (net (code "43") (name "Net-(U4A-BST_D)") (class "Default")
      (node (ref "C17") (pin "2") (pinfunction "2_2") (pintype "passive"))
      (node (ref "U4") (pin "20") (pinfunction "BST_D_20") (pintype "passive"))
    )
    (net (code "44") (name "Net-(U4A-OC_ADJ)") (class "Default")
      (node (ref "R3") (pin "1") (pinfunction "1_1") (pintype "passive"))
      (node (ref "U4") (pin "7") (pinfunction "OC_ADJ_7") (pintype "input"))
    )
    (net (code "45") (name "Net-(U4A-OUT_A)") (class "Default")
      (node (ref "C9") (pin "1") (pinfunction "1_1") (pintype "passive"))
      (node (ref "P2") (pin "1") (pinfunction "1_1") (pintype "passive"))
      (node (ref "TP9") (pin "1") (pinfunction "1_1") (pintype "passive"))
      (node (ref "U4") (pin "33") (pinfunction "OUT_A_33") (pintype "tri_state"))
    )
    (net (code "46") (name "Net-(U4A-OUT_B)") (class "Default")
      (node (ref "C15") (pin "1") (pinfunction "1_1") (pintype "passive"))
      (node (ref "P2") (pin "2") (pinfunction "2_2") (pintype "passive"))
      (node (ref "TP11") (pin "1") (pinfunction "1_1") (pintype "passive"))
      (node (ref "U4") (pin "30") (pinfunction "OUT_B_30") (pintype "tri_state"))
    )
    (net (code "47") (name "Net-(U4A-OUT_C)") (class "Default")
      (node (ref "C16") (pin "1") (pinfunction "1_1") (pintype "passive"))
      (node (ref "P2") (pin "3") (pinfunction "3_3") (pintype "passive"))
      (node (ref "TP10") (pin "1") (pinfunction "1_1") (pintype "passive"))
      (node (ref "U4") (pin "25") (pinfunction "OUT_C_25") (pintype "tri_state"))
    )
    (net (code "48") (name "Net-(U4A-OUT_D)") (class "Default")
      (node (ref "C17") (pin "1") (pinfunction "1_1") (pintype "passive"))
      (node (ref "P2") (pin "4") (pinfunction "4_4") (pintype "passive"))
      (node (ref "TP12") (pin "1") (pinfunction "1_1") (pintype "passive"))
      (node (ref "U4") (pin "22") (pinfunction "OUT_D_22") (pintype "tri_state"))
    )
    (net (code "49") (name "Net-(U4A-VREG)") (class "Default")
      (node (ref "C18") (pin "1") (pinfunction "1_1") (pintype "passive"))
      (node (ref "U4") (pin "10") (pinfunction "VREG_10") (pintype "passive"))
    )
    (net (code "50") (name "PVDD") (class "Default")
      (node (ref "C19") (pin "1") (pinfunction "P_1") (pintype "passive"))
      (node (ref "C20") (pin "1") (pinfunction "1_1") (pintype "passive"))
      (node (ref "C21") (pin "1") (pinfunction "1_1") (pintype "passive"))
      (node (ref "C22") (pin "1") (pinfunction "1_1") (pintype "passive"))
      (node (ref "C23") (pin "1") (pinfunction "1_1") (pintype "passive"))
      (node (ref "J1") (pin "2") (pinfunction "2_2") (pintype "passive"))
      (node (ref "SB1") (pin "1") (pinfunction "1_1") (pintype "passive"))
      (node (ref "SB2") (pin "1") (pinfunction "1_1") (pintype "passive"))
      (node (ref "TP1") (pin "1") (pinfunction "1_1") (pintype "passive"))
      (node (ref "U4") (pin "21") (pinfunction "PVDD_D_21") (pintype "power_in"))
      (node (ref "U4") (pin "26") (pinfunction "PVDD_C_26") (pintype "power_in"))
      (node (ref "U4") (pin "29") (pinfunction "PVDD_B_29") (pintype "power_in"))
      (node (ref "U4") (pin "34") (pinfunction "PVDD_A_34") (pintype "power_in"))
    )
    (net (code "51") (name "unconnected-(J2-SHLD-Pad3)") (class "Default")
      (node (ref "J2") (pin "3") (pinfunction "SHLD_3") (pintype "passive+no_connect"))
    )
    (net (code "52") (name "unconnected-(J2-SHLD-Pad4)") (class "Default")
      (node (ref "J2") (pin "4") (pinfunction "SHLD_4") (pintype "passive+no_connect"))
    )
    (net (code "53") (name "unconnected-(P2-Pad5)") (class "Default")
      (node (ref "P2") (pin "5") (pinfunction "5_5") (pintype "passive+no_connect"))
    )
  )
)
